# freezer_alarm.net
KiCad netlist of a schematic drawn in EAGLE
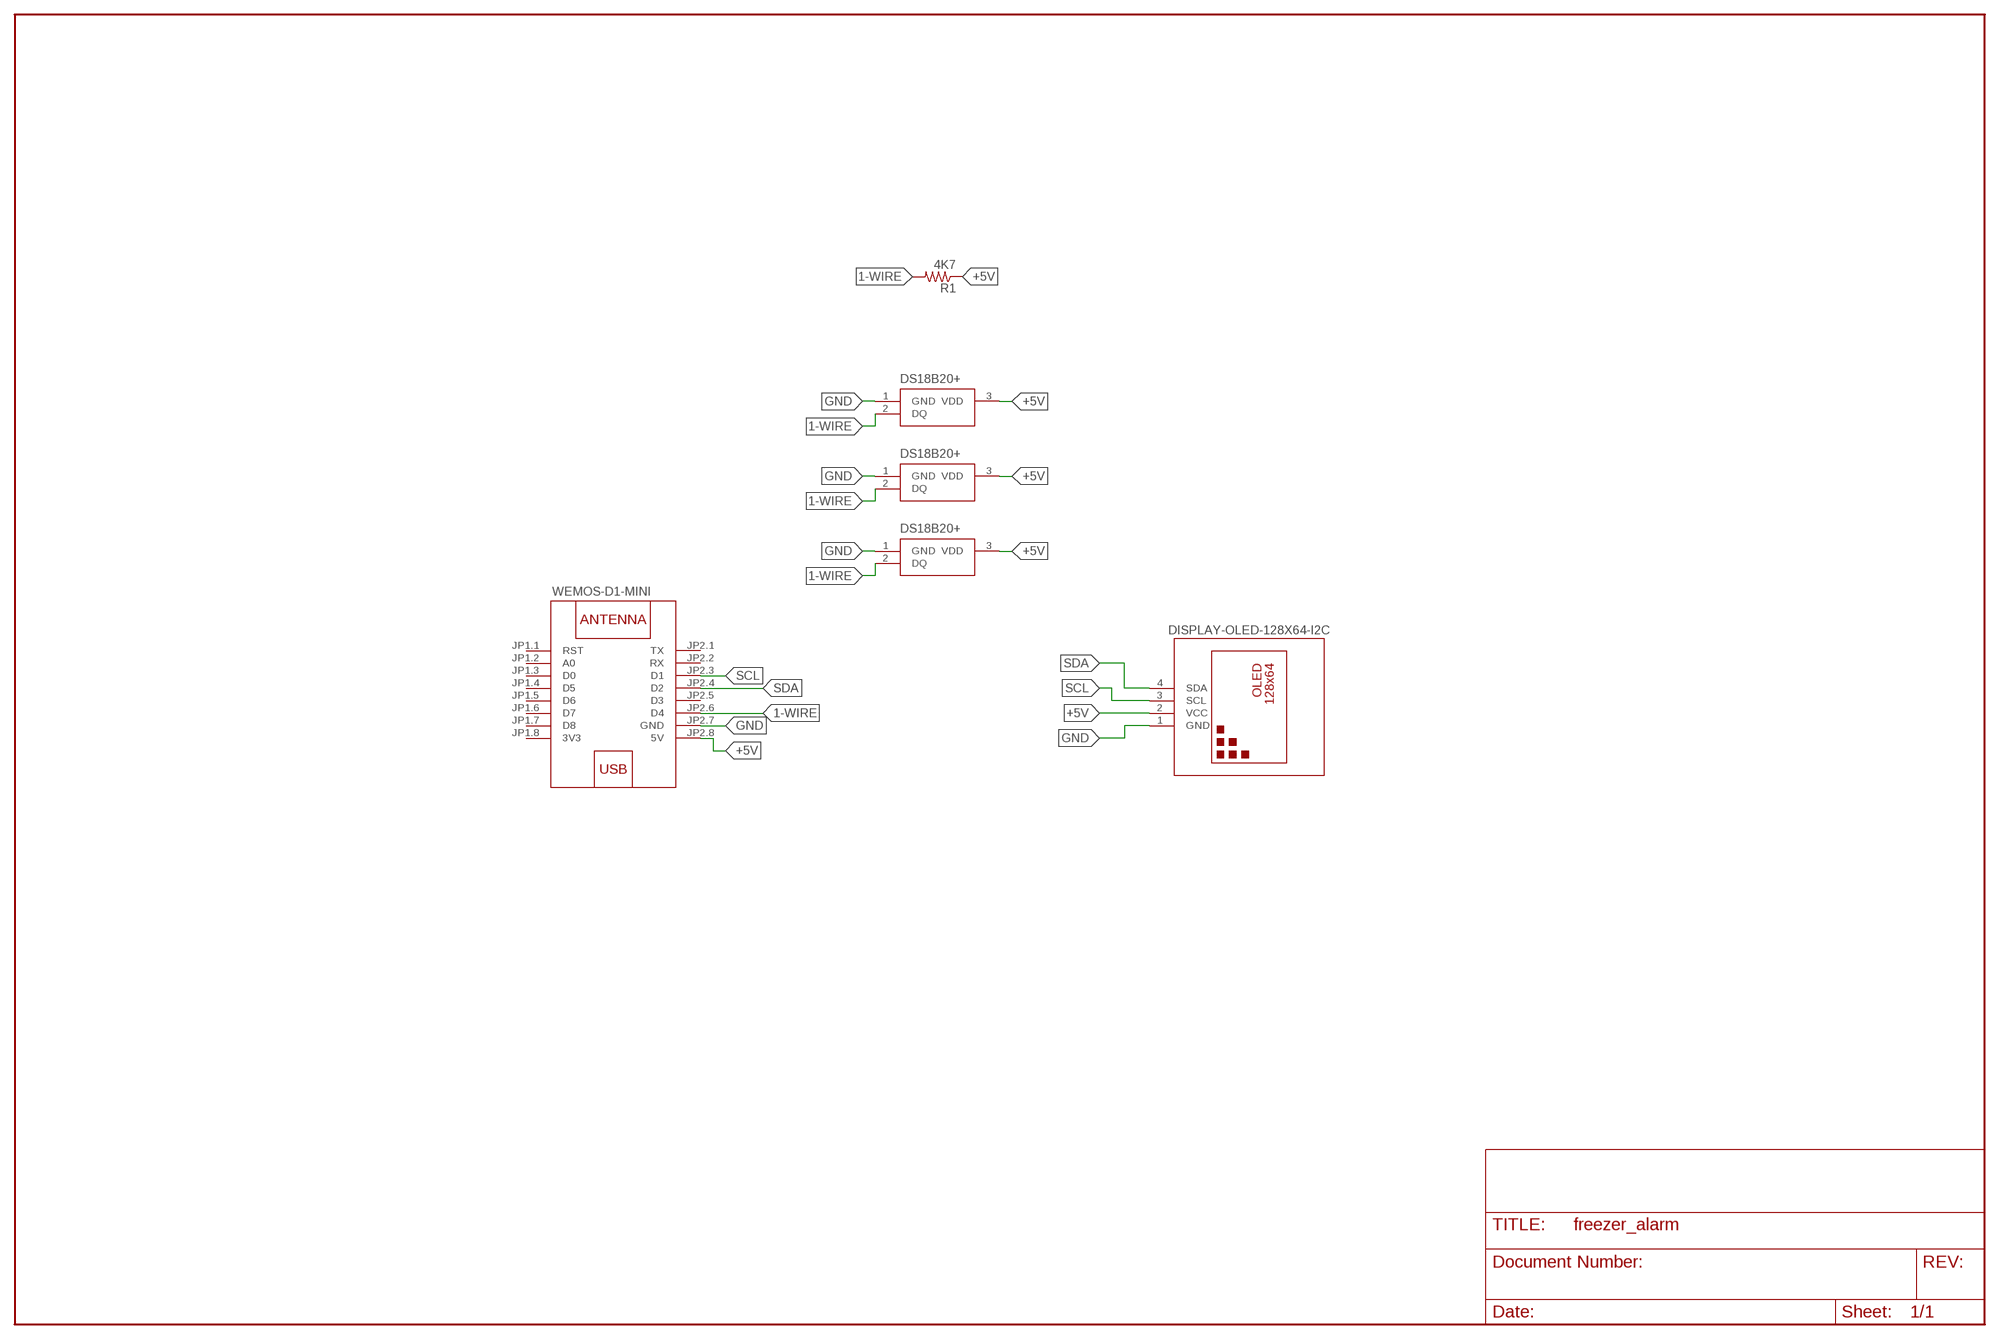
[diagram p0: schematic, sheet 1]

(export (version "E")
  (design (tool "Eeschema 10.0.6"))
  (components
    (comp (ref "DISP")
      (value "DISPLAY-OLED-128X64-I2C")
      (footprint "eagle-import:DISPLAY-OLED-128X64-I2C")
      (libsource (lib "eagle-import") (part "DISPLAY-OLED-128X64-I2C"))
    )
    (comp (ref "IC1")
      (value "DS18B20+")
      (footprint "eagle-import:TO-92")
      (fields (field (name "MOUSER_PART_NUMBER") "700-DS18B20+"))
      (libsource (lib "eagle-import") (part "DS18B20+"))
    )
    (comp (ref "IC2")
      (value "DS18B20+")
      (footprint "eagle-import:TO-92")
      (fields (field (name "MOUSER_PART_NUMBER") "700-DS18B20+"))
      (libsource (lib "eagle-import") (part "DS18B20+"))
    )
    (comp (ref "IC3")
      (value "DS18B20+")
      (footprint "eagle-import:TO-92")
      (fields (field (name "MOUSER_PART_NUMBER") "700-DS18B20+"))
      (libsource (lib "eagle-import") (part "DS18B20+"))
    )
    (comp (ref "R1")
      (value "4K7")
      (footprint "eagle-import:0207_10")
      (libsource (lib "eagle-import") (part "R-US_0207/10"))
    )
    (comp (ref "W1")
      (value "WEMOS-D1-MINI")
      (footprint "eagle-import:WEMOS-D1-MINI")
      (libsource (lib "eagle-import") (part "WEMOS-D1-MINI"))
    )
  )
  (nets
    (net (code "1") (name "+5V") (class "Default")
      (node (ref "DISP") (pin "2") (pinfunction "VCC_2") (pintype "power_in"))
      (node (ref "IC1") (pin "3") (pinfunction "VDD_3") (pintype "power_in"))
      (node (ref "IC2") (pin "3") (pinfunction "VDD_3") (pintype "power_in"))
      (node (ref "IC3") (pin "3") (pinfunction "VDD_3") (pintype "power_in"))
      (node (ref "W1") (pin "JP2.8") (pinfunction "5V_JP2.8") (pintype "power_in"))
    )
    (net (code "2") (name "/3V3") (class "Default")
      (node (ref "W1") (pin "JP1.8") (pinfunction "3V3_JP1.8") (pintype "power_in"))
    )
    (net (code "3") (name "1-WIRE") (class "Default")
      (node (ref "IC1") (pin "2") (pinfunction "DQ_2") (pintype "bidirectional"))
      (node (ref "IC2") (pin "2") (pinfunction "DQ_2") (pintype "bidirectional"))
      (node (ref "IC3") (pin "2") (pinfunction "DQ_2") (pintype "bidirectional"))
      (node (ref "W1") (pin "JP2.6") (pinfunction "D4_JP2.6") (pintype "bidirectional"))
    )
    (net (code "4") (name "GND") (class "Default")
      (node (ref "DISP") (pin "1") (pinfunction "GND_1") (pintype "power_in"))
      (node (ref "IC1") (pin "1") (pinfunction "GND_1") (pintype "power_in"))
      (node (ref "IC2") (pin "1") (pinfunction "GND_1") (pintype "power_in"))
      (node (ref "IC3") (pin "1") (pinfunction "GND_1") (pintype "power_in"))
      (node (ref "W1") (pin "JP2.7") (pinfunction "GND_JP2.7") (pintype "power_in"))
    )
    (net (code "5") (name "SCL") (class "Default")
      (node (ref "DISP") (pin "3") (pinfunction "SCL_3") (pintype "bidirectional"))
      (node (ref "W1") (pin "JP2.3") (pinfunction "D1_JP2.3") (pintype "bidirectional"))
    )
    (net (code "6") (name "SDA") (class "Default")
      (node (ref "DISP") (pin "4") (pinfunction "SDA_4") (pintype "bidirectional"))
      (node (ref "W1") (pin "JP2.4") (pinfunction "D2_JP2.4") (pintype "bidirectional"))
    )
    (net (code "7") (name "unconnected-(R1-Pad1)") (class "Default")
      (node (ref "R1") (pin "1") (pinfunction "1_1") (pintype "passive"))
    )
    (net (code "8") (name "unconnected-(R1-Pad2)") (class "Default")
      (node (ref "R1") (pin "2") (pinfunction "2_2") (pintype "passive"))
    )
    (net (code "9") (name "unconnected-(W1-A0-PadJP1.2)") (class "Default")
      (node (ref "W1") (pin "JP1.2") (pinfunction "A0_JP1.2") (pintype "bidirectional"))
    )
    (net (code "10") (name "unconnected-(W1-D0-PadJP1.3)") (class "Default")
      (node (ref "W1") (pin "JP1.3") (pinfunction "D0_JP1.3") (pintype "bidirectional"))
    )
    (net (code "11") (name "unconnected-(W1-D3-PadJP2.5)") (class "Default")
      (node (ref "W1") (pin "JP2.5") (pinfunction "D3_JP2.5") (pintype "bidirectional"))
    )
    (net (code "12") (name "unconnected-(W1-D5-PadJP1.4)") (class "Default")
      (node (ref "W1") (pin "JP1.4") (pinfunction "D5_JP1.4") (pintype "bidirectional"))
    )
    (net (code "13") (name "unconnected-(W1-D6-PadJP1.5)") (class "Default")
      (node (ref "W1") (pin "JP1.5") (pinfunction "D6_JP1.5") (pintype "bidirectional"))
    )
    (net (code "14") (name "unconnected-(W1-D7-PadJP1.6)") (class "Default")
      (node (ref "W1") (pin "JP1.6") (pinfunction "D7_JP1.6") (pintype "bidirectional"))
    )
    (net (code "15") (name "unconnected-(W1-D8-PadJP1.7)") (class "Default")
      (node (ref "W1") (pin "JP1.7") (pinfunction "D8_JP1.7") (pintype "bidirectional"))
    )
    (net (code "16") (name "unconnected-(W1-RST-PadJP1.1)") (class "Default")
      (node (ref "W1") (pin "JP1.1") (pinfunction "RST_JP1.1") (pintype "bidirectional"))
    )
    (net (code "17") (name "unconnected-(W1-RX-PadJP2.2)") (class "Default")
      (node (ref "W1") (pin "JP2.2") (pinfunction "RX_JP2.2") (pintype "bidirectional"))
    )
    (net (code "18") (name "unconnected-(W1-TX-PadJP2.1)") (class "Default")
      (node (ref "W1") (pin "JP2.1") (pinfunction "TX_JP2.1") (pintype "bidirectional"))
    )
  )
)
